# MQTT_meteo_v2_0.net
KiCad netlist of a schematic drawn in EAGLE
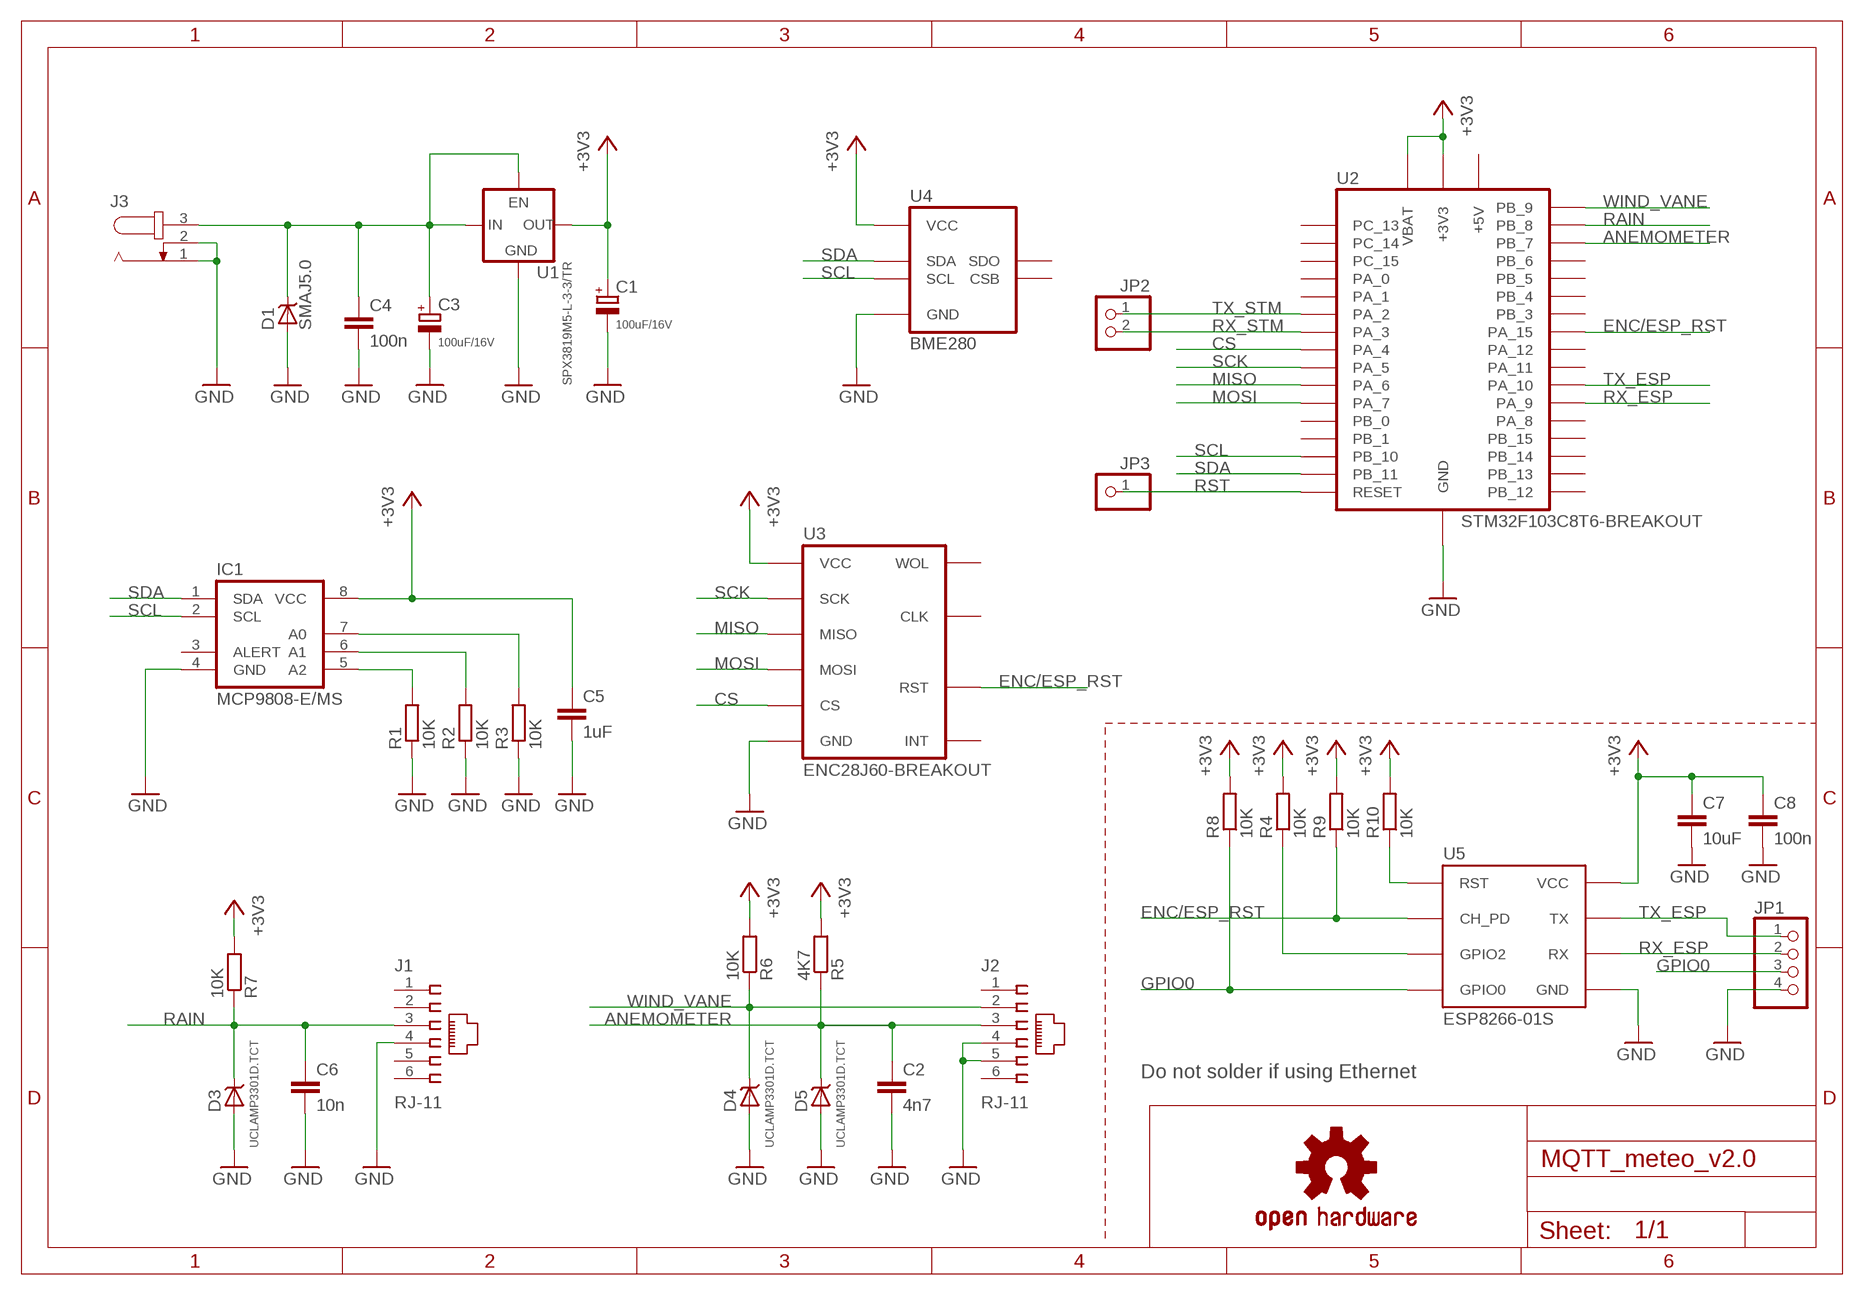
[diagram p0: schematic, sheet 1]

(export (version "E")
  (design (tool "Eeschema 10.0.6"))
  (components
    (comp (ref "C1")
      (value "100uF/16V")
      (footprint "eagle-import:E2-5")
      (libsource (lib "eagle-import") (part "CPOL-EUE2-5"))
    )
    (comp (ref "C2")
      (value "4n7")
      (footprint "eagle-import:C0805")
      (libsource (lib "eagle-import") (part "C-EUC0805"))
    )
    (comp (ref "C3")
      (value "100uF/16V")
      (footprint "eagle-import:E2-5")
      (libsource (lib "eagle-import") (part "CPOL-EUE2-5"))
    )
    (comp (ref "C4")
      (value "100n")
      (footprint "eagle-import:C0805")
      (libsource (lib "eagle-import") (part "C-EUC0805"))
    )
    (comp (ref "C5")
      (value "1uF")
      (footprint "eagle-import:C0805")
      (libsource (lib "eagle-import") (part "C-EUC0805"))
    )
    (comp (ref "C6")
      (value "10n")
      (footprint "eagle-import:C0805")
      (libsource (lib "eagle-import") (part "C-EUC0805"))
    )
    (comp (ref "C7")
      (value "10uF")
      (footprint "eagle-import:C0805")
      (libsource (lib "eagle-import") (part "C-EUC0805"))
    )
    (comp (ref "C8")
      (value "100n")
      (footprint "eagle-import:C0805")
      (libsource (lib "eagle-import") (part "C-EUC0805"))
    )
    (comp (ref "D1")
      (value "SMAJ5.0")
      (footprint "eagle-import:DO214AC")
      (libsource (lib "eagle-import") (part "SM?JA5.0"))
    )
    (comp (ref "D3")
      (value "UCLAMP3301D.TCT")
      (footprint "eagle-import:SOD323")
      (libsource (lib "eagle-import") (part "UCLAMP3301?.TCTD"))
    )
    (comp (ref "D4")
      (value "UCLAMP3301D.TCT")
      (footprint "eagle-import:SOD323")
      (libsource (lib "eagle-import") (part "UCLAMP3301?.TCTD"))
    )
    (comp (ref "D5")
      (value "UCLAMP3301D.TCT")
      (footprint "eagle-import:SOD323")
      (libsource (lib "eagle-import") (part "UCLAMP3301?.TCTD"))
    )
    (comp (ref "IC1")
      (value "MCP9808-E/MS")
      (footprint "eagle-import:MSOP8")
      (libsource (lib "eagle-import") (part "MCP9808-E/?MS"))
    )
    (comp (ref "J1")
      (value "RJ-11")
      (footprint "eagle-import:615006138421")
      (libsource (lib "eagle-import") (part "RJ-11"))
    )
    (comp (ref "J2")
      (value "RJ-11")
      (footprint "eagle-import:615006138421")
      (libsource (lib "eagle-import") (part "RJ-11"))
    )
    (comp (ref "J3")
      (value "JACK-PLUG1")
      (footprint "eagle-import:SPC4078")
      (libsource (lib "eagle-import") (part "JACK-PLUG1"))
    )
    (comp (ref "JP1")
      (value "PINHD-1X4")
      (footprint "eagle-import:1X04")
      (libsource (lib "eagle-import") (part "PINHD-1X4"))
    )
    (comp (ref "JP2")
      (value "PINHD-1X2")
      (footprint "eagle-import:1X02")
      (libsource (lib "eagle-import") (part "PINHD-1X2"))
    )
    (comp (ref "JP3")
      (value "PINHD-1X01_2.54-90°")
      (footprint "eagle-import:1X01_90")
      (libsource (lib "eagle-import") (part "PINHD-1X01_2.54-90°"))
    )
    (comp (ref "LOGO1")
      (value "OSHW-LOGOM-COPPER")
      (footprint "eagle-import:OSHW-LOGO-M_COPPER")
      (libsource (lib "eagle-import") (part "OSHW-LOGOM-COPPER"))
    )
    (comp (ref "R1")
      (value "10K")
      (footprint "eagle-import:R0805")
      (libsource (lib "eagle-import") (part "R-EU_R0805"))
    )
    (comp (ref "R2")
      (value "10K")
      (footprint "eagle-import:R0805")
      (libsource (lib "eagle-import") (part "R-EU_R0805"))
    )
    (comp (ref "R3")
      (value "10K")
      (footprint "eagle-import:R0805")
      (libsource (lib "eagle-import") (part "R-EU_R0805"))
    )
    (comp (ref "R4")
      (value "10K")
      (footprint "eagle-import:R0805")
      (libsource (lib "eagle-import") (part "R-EU_R0805"))
    )
    (comp (ref "R5")
      (value "4K7")
      (footprint "eagle-import:R0805")
      (libsource (lib "eagle-import") (part "R-EU_R0805"))
    )
    (comp (ref "R6")
      (value "10K")
      (footprint "eagle-import:R0805")
      (libsource (lib "eagle-import") (part "R-EU_R0805"))
    )
    (comp (ref "R7")
      (value "10K")
      (footprint "eagle-import:R0805")
      (libsource (lib "eagle-import") (part "R-EU_R0805"))
    )
    (comp (ref "R8")
      (value "10K")
      (footprint "eagle-import:R0805")
      (libsource (lib "eagle-import") (part "R-EU_R0805"))
    )
    (comp (ref "R9")
      (value "10K")
      (footprint "eagle-import:R0805")
      (libsource (lib "eagle-import") (part "R-EU_R0805"))
    )
    (comp (ref "R10")
      (value "10K")
      (footprint "eagle-import:R0805")
      (libsource (lib "eagle-import") (part "R-EU_R0805"))
    )
    (comp (ref "U1")
      (value "SPX3819M5-L-3-3/TR")
      (footprint "eagle-import:SOT23-5")
      (libsource (lib "eagle-import") (part "TLV700DD33"))
    )
    (comp (ref "U2")
      (value "STM32F103C8T6-BREAKOUT")
      (footprint "eagle-import:STM32F103C8T6")
      (libsource (lib "eagle-import") (part "STM32F103C8T6-BREAKOUT"))
    )
    (comp (ref "U3")
      (value "ENC28J60-BREAKOUT")
      (footprint "eagle-import:ENC28J60")
      (libsource (lib "eagle-import") (part "ENC28J60-BREAKOUT"))
    )
    (comp (ref "U4")
      (value "BME280")
      (footprint "eagle-import:BM_280")
      (libsource (lib "eagle-import") (part "BM280E"))
    )
    (comp (ref "U5")
      (value "ESP8266-01S")
      (footprint "eagle-import:ESP-01")
      (libsource (lib "eagle-import") (part "ESP8266-01S"))
    )
  )
  (nets
    (net (code "1") (name "+3V3") (class "Default")
      (node (ref "C1") (pin "+") (pinfunction "+_+") (pintype "passive"))
      (node (ref "C5") (pin "1") (pinfunction "1_1") (pintype "passive"))
      (node (ref "C7") (pin "1") (pinfunction "1_1") (pintype "passive"))
      (node (ref "C8") (pin "1") (pinfunction "1_1") (pintype "passive"))
      (node (ref "IC1") (pin "8") (pinfunction "VCC_8") (pintype "power_in"))
      (node (ref "R10") (pin "2") (pinfunction "2_2") (pintype "passive"))
      (node (ref "R4") (pin "2") (pinfunction "2_2") (pintype "passive"))
      (node (ref "R5") (pin "2") (pinfunction "2_2") (pintype "passive"))
      (node (ref "R6") (pin "2") (pinfunction "2_2") (pintype "passive"))
      (node (ref "R7") (pin "2") (pinfunction "2_2") (pintype "passive"))
      (node (ref "R8") (pin "2") (pinfunction "2_2") (pintype "passive"))
      (node (ref "R9") (pin "2") (pinfunction "2_2") (pintype "passive"))
      (node (ref "U1") (pin "5") (pinfunction "VOUT_5") (pintype "power_in"))
      (node (ref "U2") (pin "+3V3") (pinfunction "+3V3_+3V3") (pintype "power_in"))
      (node (ref "U2") (pin "+3V3@1") (pinfunction "+3V3_+3V3@1") (pintype "power_in"))
      (node (ref "U2") (pin "VBAT") (pinfunction "VBAT_VBAT") (pintype "power_in"))
      (node (ref "U3") (pin "VCC") (pinfunction "VCC_VCC") (pintype "power_in"))
      (node (ref "U4") (pin "VCC") (pinfunction "VCC_VCC") (pintype "power_in"))
      (node (ref "U5") (pin "VCC") (pinfunction "VCC_VCC") (pintype "power_in"))
    )
    (net (code "2") (name "/+5V") (class "Default")
      (node (ref "U2") (pin "+5V") (pinfunction "+5V_+5V") (pintype "power_in"))
    )
    (net (code "3") (name "/ANEMOMETER") (class "Default")
      (node (ref "C2") (pin "1") (pinfunction "1_1") (pintype "passive"))
      (node (ref "D5") (pin "C") (pinfunction "C_C") (pintype "passive"))
      (node (ref "J2") (pin "3") (pinfunction "3_3") (pintype "passive"))
      (node (ref "R5") (pin "1") (pinfunction "1_1") (pintype "passive"))
      (node (ref "U2") (pin "PB_7") (pinfunction "PB_7_PB_7") (pintype "bidirectional"))
    )
    (net (code "4") (name "/CS") (class "Default")
      (node (ref "U2") (pin "PA_4") (pinfunction "PA_4_PA_4") (pintype "bidirectional"))
      (node (ref "U3") (pin "CS") (pinfunction "CS_CS") (pintype "bidirectional"))
    )
    (net (code "5") (name "/ENC{slash}ESP_RST") (class "Default")
      (node (ref "R9") (pin "1") (pinfunction "1_1") (pintype "passive"))
      (node (ref "U2") (pin "PA_15") (pinfunction "PA_15_PA_15") (pintype "bidirectional"))
      (node (ref "U3") (pin "RST") (pinfunction "RST_RST") (pintype "bidirectional"))
      (node (ref "U5") (pin "CH_PD") (pinfunction "CH_PD_CH_PD") (pintype "bidirectional"))
    )
    (net (code "6") (name "/GPIO0") (class "Default")
      (node (ref "JP1") (pin "3") (pinfunction "3_3") (pintype "passive"))
      (node (ref "R8") (pin "1") (pinfunction "1_1") (pintype "passive"))
      (node (ref "U5") (pin "GPIO0") (pinfunction "GPIO0_GPIO0") (pintype "bidirectional"))
    )
    (net (code "7") (name "/MISO") (class "Default")
      (node (ref "U2") (pin "PA_6") (pinfunction "PA_6_PA_6") (pintype "bidirectional"))
      (node (ref "U3") (pin "SO") (pinfunction "MISO_SO") (pintype "bidirectional"))
    )
    (net (code "8") (name "/MOSI") (class "Default")
      (node (ref "U2") (pin "PA_7") (pinfunction "PA_7_PA_7") (pintype "bidirectional"))
      (node (ref "U3") (pin "SI") (pinfunction "MOSI_SI") (pintype "bidirectional"))
    )
    (net (code "9") (name "/RAIN") (class "Default")
      (node (ref "C6") (pin "1") (pinfunction "1_1") (pintype "passive"))
      (node (ref "D3") (pin "C") (pinfunction "C_C") (pintype "passive"))
      (node (ref "J1") (pin "3") (pinfunction "3_3") (pintype "passive"))
      (node (ref "R7") (pin "1") (pinfunction "1_1") (pintype "passive"))
      (node (ref "U2") (pin "PB_8") (pinfunction "PB_8_PB_8") (pintype "bidirectional"))
    )
    (net (code "10") (name "/RST") (class "Default")
      (node (ref "JP3") (pin "1") (pinfunction "1_1") (pintype "passive"))
      (node (ref "U2") (pin "RESET") (pinfunction "RESET_RESET") (pintype "input"))
    )
    (net (code "11") (name "/RX_ESP") (class "Default")
      (node (ref "JP1") (pin "2") (pinfunction "2_2") (pintype "passive"))
      (node (ref "U2") (pin "PA_9") (pinfunction "PA_9_PA_9") (pintype "bidirectional"))
      (node (ref "U5") (pin "RX") (pinfunction "RX_RX") (pintype "input"))
    )
    (net (code "12") (name "/RX_STM") (class "Default")
      (node (ref "JP2") (pin "2") (pinfunction "2_2") (pintype "passive"))
      (node (ref "U2") (pin "PA_3") (pinfunction "PA_3_PA_3") (pintype "bidirectional"))
    )
    (net (code "13") (name "/SCK") (class "Default")
      (node (ref "U2") (pin "PA_5") (pinfunction "PA_5_PA_5") (pintype "bidirectional"))
      (node (ref "U3") (pin "SCK") (pinfunction "SCK_SCK") (pintype "bidirectional"))
    )
    (net (code "14") (name "/SCL") (class "Default")
      (node (ref "IC1") (pin "2") (pinfunction "SCL_2") (pintype "bidirectional"))
      (node (ref "U2") (pin "PB_10") (pinfunction "PB_10_PB_10") (pintype "bidirectional"))
      (node (ref "U4") (pin "SCL") (pinfunction "SCL_SCL") (pintype "bidirectional"))
    )
    (net (code "15") (name "/SDA") (class "Default")
      (node (ref "IC1") (pin "1") (pinfunction "SDA_1") (pintype "bidirectional"))
      (node (ref "U2") (pin "PB_11") (pinfunction "PB_11_PB_11") (pintype "bidirectional"))
      (node (ref "U4") (pin "SDA") (pinfunction "SDA_SDA") (pintype "bidirectional"))
    )
    (net (code "16") (name "/TX_ESP") (class "Default")
      (node (ref "JP1") (pin "1") (pinfunction "1_1") (pintype "passive"))
      (node (ref "U2") (pin "PA_10") (pinfunction "PA_10_PA_10") (pintype "bidirectional"))
      (node (ref "U5") (pin "TX") (pinfunction "TX_TX") (pintype "output"))
    )
    (net (code "17") (name "/TX_STM") (class "Default")
      (node (ref "JP2") (pin "1") (pinfunction "1_1") (pintype "passive"))
      (node (ref "U2") (pin "PA_2") (pinfunction "PA_2_PA_2") (pintype "bidirectional"))
    )
    (net (code "18") (name "/WIND_VANE") (class "Default")
      (node (ref "D4") (pin "C") (pinfunction "C_C") (pintype "passive"))
      (node (ref "J2") (pin "2") (pinfunction "2_2") (pintype "passive"))
      (node (ref "R6") (pin "1") (pinfunction "1_1") (pintype "passive"))
      (node (ref "U2") (pin "PB_9") (pinfunction "PB_9_PB_9") (pintype "bidirectional"))
    )
    (net (code "19") (name "GND") (class "Default")
      (node (ref "C1") (pin "-") (pinfunction "-_-") (pintype "passive"))
      (node (ref "C2") (pin "2") (pinfunction "2_2") (pintype "passive"))
      (node (ref "C3") (pin "-") (pinfunction "-_-") (pintype "passive"))
      (node (ref "C4") (pin "2") (pinfunction "2_2") (pintype "passive"))
      (node (ref "C5") (pin "2") (pinfunction "2_2") (pintype "passive"))
      (node (ref "C6") (pin "2") (pinfunction "2_2") (pintype "passive"))
      (node (ref "C7") (pin "2") (pinfunction "2_2") (pintype "passive"))
      (node (ref "C8") (pin "2") (pinfunction "2_2") (pintype "passive"))
      (node (ref "D1") (pin "A") (pinfunction "A_A") (pintype "passive"))
      (node (ref "D3") (pin "A") (pinfunction "A_A") (pintype "passive"))
      (node (ref "D4") (pin "A") (pinfunction "A_A") (pintype "passive"))
      (node (ref "D5") (pin "A") (pinfunction "A_A") (pintype "passive"))
      (node (ref "IC1") (pin "4") (pinfunction "GND_4") (pintype "power_in"))
      (node (ref "J1") (pin "4") (pinfunction "4_4") (pintype "passive"))
      (node (ref "J2") (pin "4") (pinfunction "4_4") (pintype "passive"))
      (node (ref "J2") (pin "5") (pinfunction "5_5") (pintype "passive"))
      (node (ref "J3") (pin "1") (pinfunction "1_1") (pintype "passive"))
      (node (ref "J3") (pin "2") (pinfunction "2_2") (pintype "passive"))
      (node (ref "JP1") (pin "4") (pinfunction "4_4") (pintype "passive"))
      (node (ref "R1") (pin "1") (pinfunction "1_1") (pintype "passive"))
      (node (ref "R2") (pin "1") (pinfunction "1_1") (pintype "passive"))
      (node (ref "R3") (pin "1") (pinfunction "1_1") (pintype "passive"))
      (node (ref "U1") (pin "2") (pinfunction "GND_2") (pintype "power_in"))
      (node (ref "U2") (pin "GND") (pinfunction "GND_GND") (pintype "power_in"))
      (node (ref "U2") (pin "GND@1") (pinfunction "GND_GND@1") (pintype "power_in"))
      (node (ref "U2") (pin "GND@2") (pinfunction "GND_GND@2") (pintype "power_in"))
      (node (ref "U3") (pin "GND") (pinfunction "GND_GND") (pintype "power_in"))
      (node (ref "U4") (pin "GND") (pinfunction "GND_GND") (pintype "power_in"))
      (node (ref "U5") (pin "GND") (pinfunction "GND_GND") (pintype "power_in"))
    )
    (net (code "20") (name "Net-(IC1-A0)") (class "Default")
      (node (ref "IC1") (pin "7") (pinfunction "A0_7") (pintype "input"))
      (node (ref "R3") (pin "2") (pinfunction "2_2") (pintype "passive"))
    )
    (net (code "21") (name "Net-(IC1-A1)") (class "Default")
      (node (ref "IC1") (pin "6") (pinfunction "A1_6") (pintype "input"))
      (node (ref "R2") (pin "2") (pinfunction "2_2") (pintype "passive"))
    )
    (net (code "22") (name "Net-(IC1-A2)") (class "Default")
      (node (ref "IC1") (pin "5") (pinfunction "A2_5") (pintype "input"))
      (node (ref "R1") (pin "2") (pinfunction "2_2") (pintype "passive"))
    )
    (net (code "23") (name "Net-(R4-Pad1)") (class "Default")
      (node (ref "R4") (pin "1") (pinfunction "1_1") (pintype "passive"))
      (node (ref "U5") (pin "GPIO2") (pinfunction "GPIO2_GPIO2") (pintype "bidirectional"))
    )
    (net (code "24") (name "Net-(R10-Pad1)") (class "Default")
      (node (ref "R10") (pin "1") (pinfunction "1_1") (pintype "passive"))
      (node (ref "U5") (pin "RST") (pinfunction "RST_RST") (pintype "bidirectional"))
    )
    (net (code "25") (name "Net-(U1-EN)") (class "Default")
      (node (ref "C3") (pin "+") (pinfunction "+_+") (pintype "passive"))
      (node (ref "C4") (pin "1") (pinfunction "1_1") (pintype "passive"))
      (node (ref "D1") (pin "C") (pinfunction "C_C") (pintype "passive"))
      (node (ref "J3") (pin "3") (pinfunction "3_3") (pintype "passive"))
      (node (ref "U1") (pin "1") (pinfunction "VIN_1") (pintype "power_in"))
      (node (ref "U1") (pin "3") (pinfunction "EN_3") (pintype "input"))
    )
    (net (code "26") (name "unconnected-(IC1-ALERT-Pad3)") (class "Default")
      (node (ref "IC1") (pin "3") (pinfunction "ALERT_3") (pintype "open_collector"))
    )
    (net (code "27") (name "unconnected-(J1-Pad1)") (class "Default")
      (node (ref "J1") (pin "1") (pinfunction "1_1") (pintype "passive"))
    )
    (net (code "28") (name "unconnected-(J1-Pad2)") (class "Default")
      (node (ref "J1") (pin "2") (pinfunction "2_2") (pintype "passive"))
    )
    (net (code "29") (name "unconnected-(J1-Pad5)") (class "Default")
      (node (ref "J1") (pin "5") (pinfunction "5_5") (pintype "passive"))
    )
    (net (code "30") (name "unconnected-(J1-Pad6)") (class "Default")
      (node (ref "J1") (pin "6") (pinfunction "6_6") (pintype "passive"))
    )
    (net (code "31") (name "unconnected-(J2-Pad1)") (class "Default")
      (node (ref "J2") (pin "1") (pinfunction "1_1") (pintype "passive"))
    )
    (net (code "32") (name "unconnected-(J2-Pad6)") (class "Default")
      (node (ref "J2") (pin "6") (pinfunction "6_6") (pintype "passive"))
    )
    (net (code "33") (name "unconnected-(U2-PadPA_0)") (class "Default")
      (node (ref "U2") (pin "PA_0") (pinfunction "PA_0_PA_0") (pintype "bidirectional"))
    )
    (net (code "34") (name "unconnected-(U2-PadPA_1)") (class "Default")
      (node (ref "U2") (pin "PA_1") (pinfunction "PA_1_PA_1") (pintype "bidirectional"))
    )
    (net (code "35") (name "unconnected-(U2-PadPA_8)") (class "Default")
      (node (ref "U2") (pin "PA_8") (pinfunction "PA_8_PA_8") (pintype "bidirectional"))
    )
    (net (code "36") (name "unconnected-(U2-PadPA_11)") (class "Default")
      (node (ref "U2") (pin "PA_11") (pinfunction "PA_11_PA_11") (pintype "bidirectional"))
    )
    (net (code "37") (name "unconnected-(U2-PadPA_12)") (class "Default")
      (node (ref "U2") (pin "PA_12") (pinfunction "PA_12_PA_12") (pintype "bidirectional"))
    )
    (net (code "38") (name "unconnected-(U2-PadPB_0)") (class "Default")
      (node (ref "U2") (pin "PB_0") (pinfunction "PB_0_PB_0") (pintype "bidirectional"))
    )
    (net (code "39") (name "unconnected-(U2-PadPB_1)") (class "Default")
      (node (ref "U2") (pin "PB_1") (pinfunction "PB_1_PB_1") (pintype "bidirectional"))
    )
    (net (code "40") (name "unconnected-(U2-PadPB_3)") (class "Default")
      (node (ref "U2") (pin "PB_3") (pinfunction "PB_3_PB_3") (pintype "bidirectional"))
    )
    (net (code "41") (name "unconnected-(U2-PadPB_4)") (class "Default")
      (node (ref "U2") (pin "PB_4") (pinfunction "PB_4_PB_4") (pintype "bidirectional"))
    )
    (net (code "42") (name "unconnected-(U2-PadPB_5)") (class "Default")
      (node (ref "U2") (pin "PB_5") (pinfunction "PB_5_PB_5") (pintype "bidirectional"))
    )
    (net (code "43") (name "unconnected-(U2-PadPB_6)") (class "Default")
      (node (ref "U2") (pin "PB_6") (pinfunction "PB_6_PB_6") (pintype "bidirectional"))
    )
    (net (code "44") (name "unconnected-(U2-PadPB_12)") (class "Default")
      (node (ref "U2") (pin "PB_12") (pinfunction "PB_12_PB_12") (pintype "bidirectional"))
    )
    (net (code "45") (name "unconnected-(U2-PadPB_13)") (class "Default")
      (node (ref "U2") (pin "PB_13") (pinfunction "PB_13_PB_13") (pintype "bidirectional"))
    )
    (net (code "46") (name "unconnected-(U2-PadPB_14)") (class "Default")
      (node (ref "U2") (pin "PB_14") (pinfunction "PB_14_PB_14") (pintype "bidirectional"))
    )
    (net (code "47") (name "unconnected-(U2-PadPB_15)") (class "Default")
      (node (ref "U2") (pin "PB_15") (pinfunction "PB_15_PB_15") (pintype "bidirectional"))
    )
    (net (code "48") (name "unconnected-(U2-PadPC_13)") (class "Default")
      (node (ref "U2") (pin "PC_13") (pinfunction "PC_13_PC_13") (pintype "bidirectional"))
    )
    (net (code "49") (name "unconnected-(U2-PadPC_14)") (class "Default")
      (node (ref "U2") (pin "PC_14") (pinfunction "PC_14_PC_14") (pintype "bidirectional"))
    )
    (net (code "50") (name "unconnected-(U2-PadPC_15)") (class "Default")
      (node (ref "U2") (pin "PC_15") (pinfunction "PC_15_PC_15") (pintype "bidirectional"))
    )
    (net (code "51") (name "unconnected-(U3-INT-PadNT)") (class "Default")
      (node (ref "U3") (pin "NT") (pinfunction "INT_NT") (pintype "bidirectional"))
    )
    (net (code "52") (name "unconnected-(U3-PadCLK)") (class "Default")
      (node (ref "U3") (pin "CLK") (pinfunction "CLK_CLK") (pintype "bidirectional"))
    )
    (net (code "53") (name "unconnected-(U3-PadWOL)") (class "Default")
      (node (ref "U3") (pin "WOL") (pinfunction "WOL_WOL") (pintype "bidirectional"))
    )
    (net (code "54") (name "unconnected-(U4-PadCSB)") (class "Default")
      (node (ref "U4") (pin "CSB") (pinfunction "CSB_CSB") (pintype "bidirectional"))
    )
    (net (code "55") (name "unconnected-(U4-PadSDO)") (class "Default")
      (node (ref "U4") (pin "SDO") (pinfunction "SDO_SDO") (pintype "bidirectional"))
    )
  )
)
